# Right_Glove.net
KiCad netlist of a schematic drawn in EAGLE
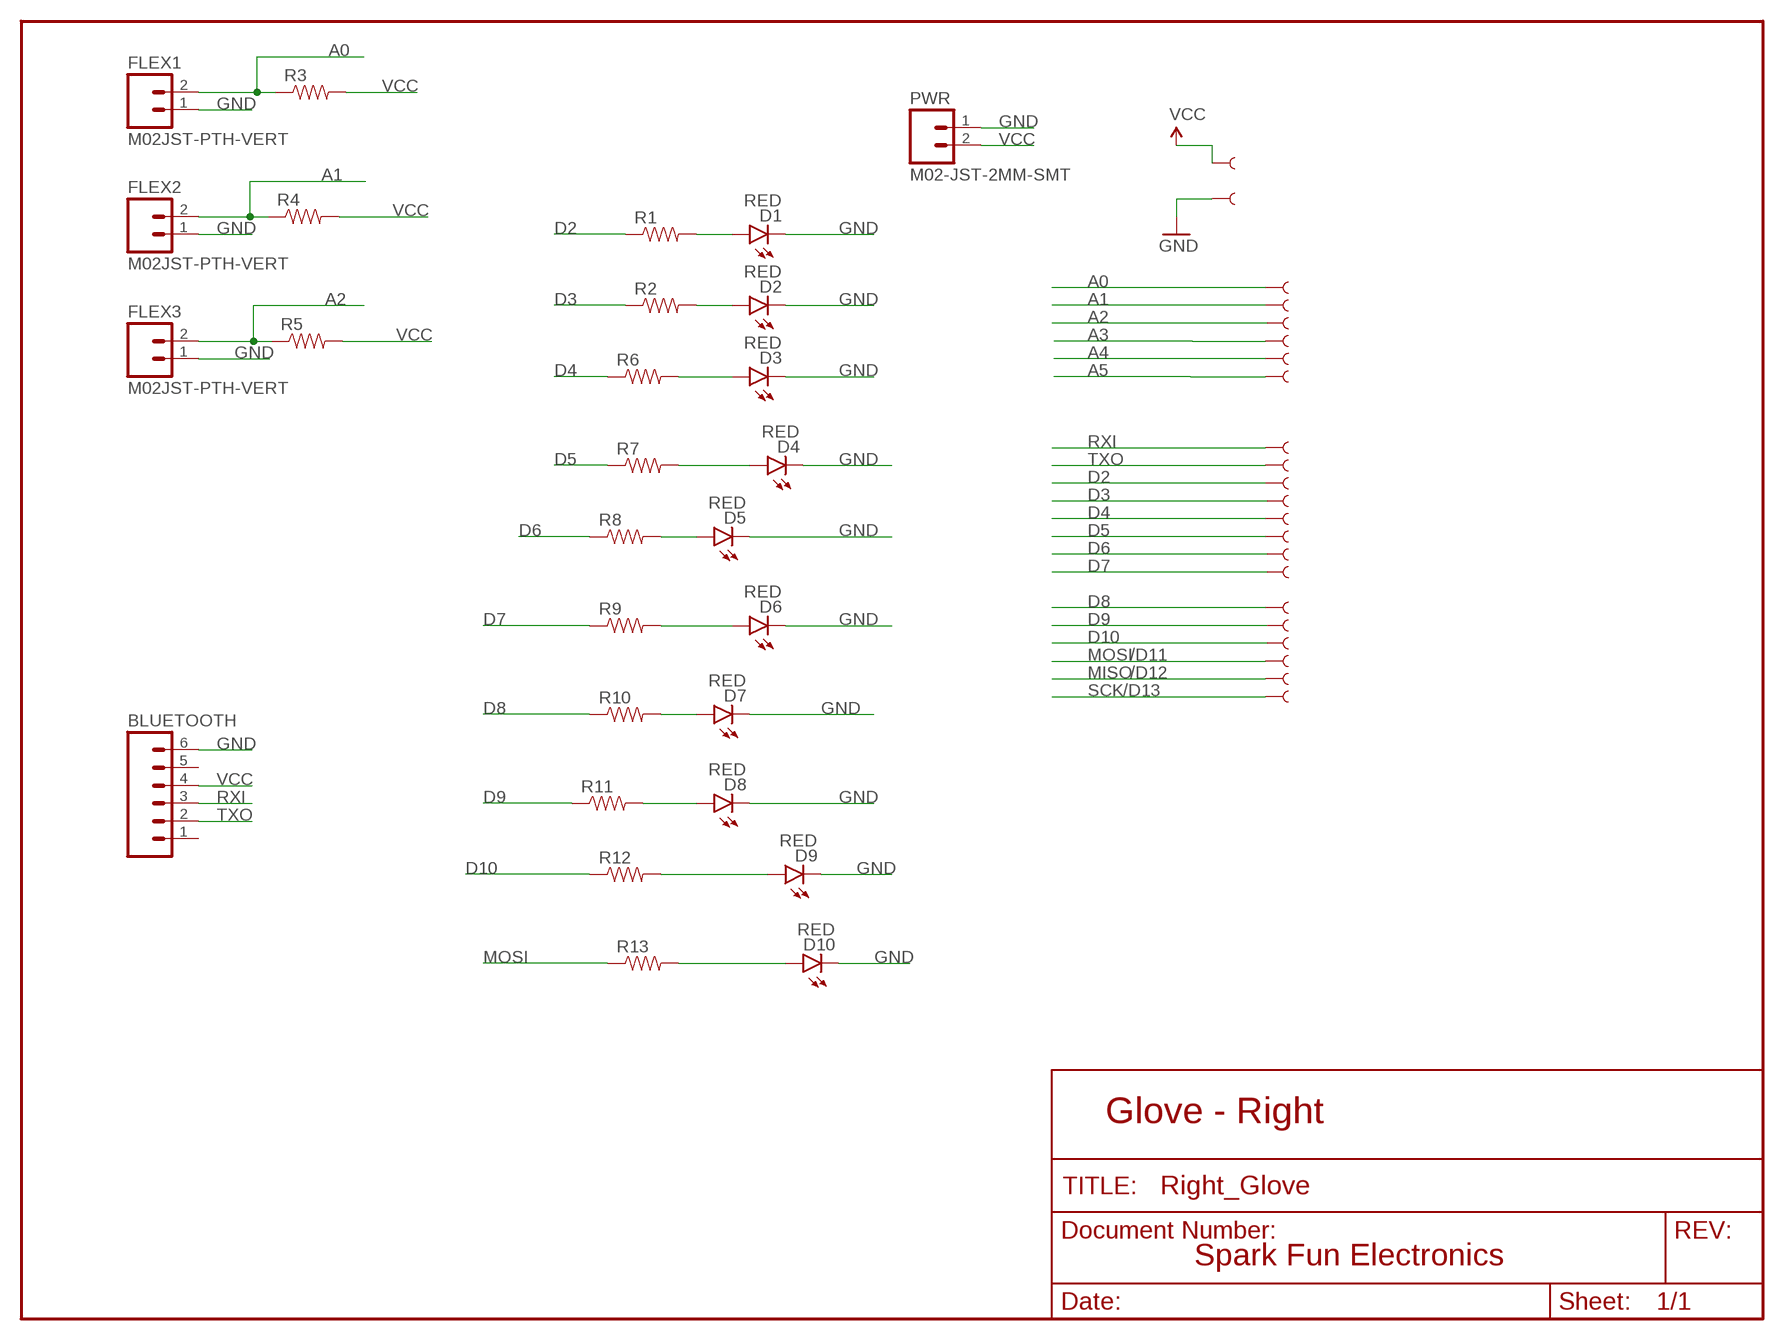
[diagram p0: schematic, sheet 1]

(export (version "E")
  (design (tool "Eeschema 10.0.6"))
  (components
    (comp (ref "BLUETOOTH")
      (value "M06LOCK")
      (footprint "eagle-import:1X06_LOCK")
      (libsource (lib "eagle-import") (part "M06LOCK"))
    )
    (comp (ref "D1")
      (value "RED")
      (footprint "eagle-import:LED-1206")
      (libsource (lib "eagle-import") (part "LED-RED1206"))
    )
    (comp (ref "D2")
      (value "RED")
      (footprint "eagle-import:LED-1206")
      (libsource (lib "eagle-import") (part "LED-RED1206"))
    )
    (comp (ref "D3")
      (value "RED")
      (footprint "eagle-import:LED-1206")
      (libsource (lib "eagle-import") (part "LED-RED1206"))
    )
    (comp (ref "D4")
      (value "RED")
      (footprint "eagle-import:LED-1206")
      (libsource (lib "eagle-import") (part "LED-RED1206"))
    )
    (comp (ref "D5")
      (value "RED")
      (footprint "eagle-import:LED-1206")
      (libsource (lib "eagle-import") (part "LED-RED1206"))
    )
    (comp (ref "D6")
      (value "RED")
      (footprint "eagle-import:LED-1206")
      (libsource (lib "eagle-import") (part "LED-RED1206"))
    )
    (comp (ref "D7")
      (value "RED")
      (footprint "eagle-import:LED-1206")
      (libsource (lib "eagle-import") (part "LED-RED1206"))
    )
    (comp (ref "D8")
      (value "RED")
      (footprint "eagle-import:LED-1206")
      (libsource (lib "eagle-import") (part "LED-RED1206"))
    )
    (comp (ref "D9")
      (value "RED")
      (footprint "eagle-import:LED-1206")
      (libsource (lib "eagle-import") (part "LED-RED1206"))
    )
    (comp (ref "D10")
      (value "RED")
      (footprint "eagle-import:LED-1206")
      (libsource (lib "eagle-import") (part "LED-RED1206"))
    )
    (comp (ref "FLEX1")
      (value "M02JST-PTH-VERT")
      (footprint "eagle-import:JST-2-PTH-VERT")
      (libsource (lib "eagle-import") (part "M02JST-PTH-VERT"))
    )
    (comp (ref "FLEX2")
      (value "M02JST-PTH-VERT")
      (footprint "eagle-import:JST-2-PTH-VERT")
      (libsource (lib "eagle-import") (part "M02JST-PTH-VERT"))
    )
    (comp (ref "FLEX3")
      (value "M02JST-PTH-VERT")
      (footprint "eagle-import:JST-2-PTH-VERT")
      (libsource (lib "eagle-import") (part "M02JST-PTH-VERT"))
    )
    (comp (ref "PWR")
      (value "M02-JST-2MM-SMT")
      (footprint "eagle-import:JST-2-SMD")
      (libsource (lib "eagle-import") (part "M02-JST-2MM-SMT"))
    )
    (comp (ref "R1")
      (value "RESISTOR1206")
      (footprint "eagle-import:1206")
      (libsource (lib "eagle-import") (part "RESISTOR1206"))
    )
    (comp (ref "R2")
      (value "RESISTOR1206")
      (footprint "eagle-import:1206")
      (libsource (lib "eagle-import") (part "RESISTOR1206"))
    )
    (comp (ref "R3")
      (value "RESISTOR1206")
      (footprint "eagle-import:1206")
      (libsource (lib "eagle-import") (part "RESISTOR1206"))
    )
    (comp (ref "R4")
      (value "RESISTOR1206")
      (footprint "eagle-import:1206")
      (libsource (lib "eagle-import") (part "RESISTOR1206"))
    )
    (comp (ref "R5")
      (value "RESISTOR1206")
      (footprint "eagle-import:1206")
      (libsource (lib "eagle-import") (part "RESISTOR1206"))
    )
    (comp (ref "R6")
      (value "RESISTOR1206")
      (footprint "eagle-import:1206")
      (libsource (lib "eagle-import") (part "RESISTOR1206"))
    )
    (comp (ref "R7")
      (value "RESISTOR1206")
      (footprint "eagle-import:1206")
      (libsource (lib "eagle-import") (part "RESISTOR1206"))
    )
    (comp (ref "R8")
      (value "RESISTOR1206")
      (footprint "eagle-import:1206")
      (libsource (lib "eagle-import") (part "RESISTOR1206"))
    )
    (comp (ref "R9")
      (value "RESISTOR1206")
      (footprint "eagle-import:1206")
      (libsource (lib "eagle-import") (part "RESISTOR1206"))
    )
    (comp (ref "R10")
      (value "RESISTOR1206")
      (footprint "eagle-import:1206")
      (libsource (lib "eagle-import") (part "RESISTOR1206"))
    )
    (comp (ref "R11")
      (value "RESISTOR1206")
      (footprint "eagle-import:1206")
      (libsource (lib "eagle-import") (part "RESISTOR1206"))
    )
    (comp (ref "R12")
      (value "RESISTOR1206")
      (footprint "eagle-import:1206")
      (libsource (lib "eagle-import") (part "RESISTOR1206"))
    )
    (comp (ref "R13")
      (value "RESISTOR1206")
      (footprint "eagle-import:1206")
      (libsource (lib "eagle-import") (part "RESISTOR1206"))
    )
    (comp (ref "U$22")
      (value "SEWTAP1")
      (footprint "eagle-import:PETAL-LONG-1")
      (libsource (lib "eagle-import") (part "SEWTAP1"))
    )
    (comp (ref "U$23")
      (value "SEWTAP1")
      (footprint "eagle-import:PETAL-LONG-1")
      (libsource (lib "eagle-import") (part "SEWTAP1"))
    )
    (comp (ref "U$24")
      (value "SEWTAP1")
      (footprint "eagle-import:PETAL-LONG-1")
      (libsource (lib "eagle-import") (part "SEWTAP1"))
    )
    (comp (ref "U$26")
      (value "SEWTAP1")
      (footprint "eagle-import:PETAL-LONG-1")
      (libsource (lib "eagle-import") (part "SEWTAP1"))
    )
    (comp (ref "U$27")
      (value "SEWTAP1")
      (footprint "eagle-import:PETAL-LONG-1")
      (libsource (lib "eagle-import") (part "SEWTAP1"))
    )
    (comp (ref "U$28")
      (value "SEWTAP1")
      (footprint "eagle-import:PETAL-LONG-1")
      (libsource (lib "eagle-import") (part "SEWTAP1"))
    )
    (comp (ref "U$29")
      (value "SEWTAP1")
      (footprint "eagle-import:PETAL-LONG-1")
      (libsource (lib "eagle-import") (part "SEWTAP1"))
    )
    (comp (ref "U$30")
      (value "SEWTAP1")
      (footprint "eagle-import:PETAL-LONG-1")
      (libsource (lib "eagle-import") (part "SEWTAP1"))
    )
    (comp (ref "U$31")
      (value "SEWTAP1")
      (footprint "eagle-import:PETAL-LONG-1")
      (libsource (lib "eagle-import") (part "SEWTAP1"))
    )
    (comp (ref "U$32")
      (value "SEWTAP1")
      (footprint "eagle-import:PETAL-LONG-1")
      (libsource (lib "eagle-import") (part "SEWTAP1"))
    )
    (comp (ref "U$33")
      (value "SEWTAP1")
      (footprint "eagle-import:PETAL-LONG-1")
      (libsource (lib "eagle-import") (part "SEWTAP1"))
    )
    (comp (ref "U$34")
      (value "SEWTAP1")
      (footprint "eagle-import:PETAL-LONG-1")
      (libsource (lib "eagle-import") (part "SEWTAP1"))
    )
    (comp (ref "U$35")
      (value "SEWTAP1")
      (footprint "eagle-import:PETAL-LONG-1")
      (libsource (lib "eagle-import") (part "SEWTAP1"))
    )
    (comp (ref "U$36")
      (value "SEWTAP1")
      (footprint "eagle-import:PETAL-LONG-1")
      (libsource (lib "eagle-import") (part "SEWTAP1"))
    )
    (comp (ref "U$37")
      (value "SEWTAP1")
      (footprint "eagle-import:PETAL-LONG-1")
      (libsource (lib "eagle-import") (part "SEWTAP1"))
    )
    (comp (ref "U$38")
      (value "SEWTAP1")
      (footprint "eagle-import:PETAL-LONG-1")
      (libsource (lib "eagle-import") (part "SEWTAP1"))
    )
    (comp (ref "U$39")
      (value "SEWTAP1")
      (footprint "eagle-import:PETAL-LONG-1")
      (libsource (lib "eagle-import") (part "SEWTAP1"))
    )
    (comp (ref "U$40")
      (value "SEWTAP1")
      (footprint "eagle-import:PETAL-LONG-1")
      (libsource (lib "eagle-import") (part "SEWTAP1"))
    )
    (comp (ref "U$41")
      (value "SEWTAP1")
      (footprint "eagle-import:PETAL-LONG-1")
      (libsource (lib "eagle-import") (part "SEWTAP1"))
    )
    (comp (ref "U$42")
      (value "SEWTAP1")
      (footprint "eagle-import:PETAL-LONG-1")
      (libsource (lib "eagle-import") (part "SEWTAP1"))
    )
    (comp (ref "U$43")
      (value "SEWTAP1")
      (footprint "eagle-import:PETAL-LONG-1")
      (libsource (lib "eagle-import") (part "SEWTAP1"))
    )
    (comp (ref "U$44")
      (value "SEWTAP1")
      (footprint "eagle-import:PETAL-LONG-1")
      (libsource (lib "eagle-import") (part "SEWTAP1"))
    )
  )
  (nets
    (net (code "1") (name "/A0") (class "Default")
      (node (ref "FLEX1") (pin "2") (pinfunction "2_2") (pintype "passive"))
      (node (ref "R3") (pin "1") (pinfunction "1_1") (pintype "passive"))
      (node (ref "U$24") (pin "P$1") (pinfunction "1_P$1") (pintype "bidirectional"))
    )
    (net (code "2") (name "/A1") (class "Default")
      (node (ref "FLEX2") (pin "2") (pinfunction "2_2") (pintype "passive"))
      (node (ref "R4") (pin "1") (pinfunction "1_1") (pintype "passive"))
      (node (ref "U$26") (pin "P$1") (pinfunction "1_P$1") (pintype "bidirectional"))
    )
    (net (code "3") (name "/A2") (class "Default")
      (node (ref "FLEX3") (pin "2") (pinfunction "2_2") (pintype "passive"))
      (node (ref "R5") (pin "1") (pinfunction "1_1") (pintype "passive"))
      (node (ref "U$27") (pin "P$1") (pinfunction "1_P$1") (pintype "bidirectional"))
    )
    (net (code "4") (name "/A3") (class "Default")
      (node (ref "U$28") (pin "P$1") (pinfunction "1_P$1") (pintype "bidirectional"))
    )
    (net (code "5") (name "/A4") (class "Default")
      (node (ref "U$29") (pin "P$1") (pinfunction "1_P$1") (pintype "bidirectional"))
    )
    (net (code "6") (name "/A5") (class "Default")
      (node (ref "U$30") (pin "P$1") (pinfunction "1_P$1") (pintype "bidirectional"))
    )
    (net (code "7") (name "/D2") (class "Default")
      (node (ref "R1") (pin "1") (pinfunction "1_1") (pintype "passive"))
      (node (ref "U$33") (pin "P$1") (pinfunction "1_P$1") (pintype "bidirectional"))
    )
    (net (code "8") (name "/D3") (class "Default")
      (node (ref "R2") (pin "1") (pinfunction "1_1") (pintype "passive"))
      (node (ref "U$34") (pin "P$1") (pinfunction "1_P$1") (pintype "bidirectional"))
    )
    (net (code "9") (name "/D4") (class "Default")
      (node (ref "R6") (pin "1") (pinfunction "1_1") (pintype "passive"))
      (node (ref "U$35") (pin "P$1") (pinfunction "1_P$1") (pintype "bidirectional"))
    )
    (net (code "10") (name "/D5") (class "Default")
      (node (ref "R7") (pin "1") (pinfunction "1_1") (pintype "passive"))
      (node (ref "U$36") (pin "P$1") (pinfunction "1_P$1") (pintype "bidirectional"))
    )
    (net (code "11") (name "/D6") (class "Default")
      (node (ref "R8") (pin "1") (pinfunction "1_1") (pintype "passive"))
      (node (ref "U$37") (pin "P$1") (pinfunction "1_P$1") (pintype "bidirectional"))
    )
    (net (code "12") (name "/D7") (class "Default")
      (node (ref "R9") (pin "1") (pinfunction "1_1") (pintype "passive"))
      (node (ref "U$38") (pin "P$1") (pinfunction "1_P$1") (pintype "bidirectional"))
    )
    (net (code "13") (name "/D8") (class "Default")
      (node (ref "R10") (pin "1") (pinfunction "1_1") (pintype "passive"))
      (node (ref "U$39") (pin "P$1") (pinfunction "1_P$1") (pintype "bidirectional"))
    )
    (net (code "14") (name "/D9") (class "Default")
      (node (ref "R11") (pin "1") (pinfunction "1_1") (pintype "passive"))
      (node (ref "U$40") (pin "P$1") (pinfunction "1_P$1") (pintype "bidirectional"))
    )
    (net (code "15") (name "/D10") (class "Default")
      (node (ref "R12") (pin "1") (pinfunction "1_1") (pintype "passive"))
      (node (ref "U$41") (pin "P$1") (pinfunction "1_P$1") (pintype "bidirectional"))
    )
    (net (code "16") (name "/MISO") (class "Default")
      (node (ref "U$43") (pin "P$1") (pinfunction "1_P$1") (pintype "bidirectional"))
    )
    (net (code "17") (name "/MOSI") (class "Default")
      (node (ref "R13") (pin "1") (pinfunction "1_1") (pintype "passive"))
      (node (ref "U$42") (pin "P$1") (pinfunction "1_P$1") (pintype "bidirectional"))
    )
    (net (code "18") (name "/RXI") (class "Default")
      (node (ref "BLUETOOTH") (pin "3") (pinfunction "3_3") (pintype "passive"))
      (node (ref "U$31") (pin "P$1") (pinfunction "1_P$1") (pintype "bidirectional"))
    )
    (net (code "19") (name "/SCK") (class "Default")
      (node (ref "U$44") (pin "P$1") (pinfunction "1_P$1") (pintype "bidirectional"))
    )
    (net (code "20") (name "/TXO") (class "Default")
      (node (ref "BLUETOOTH") (pin "2") (pinfunction "2_2") (pintype "passive"))
      (node (ref "U$32") (pin "P$1") (pinfunction "1_P$1") (pintype "bidirectional"))
    )
    (net (code "21") (name "GND") (class "Default")
      (node (ref "BLUETOOTH") (pin "6") (pinfunction "6_6") (pintype "passive"))
      (node (ref "D1") (pin "C") (pinfunction "C_C") (pintype "passive"))
      (node (ref "D10") (pin "C") (pinfunction "C_C") (pintype "passive"))
      (node (ref "D2") (pin "C") (pinfunction "C_C") (pintype "passive"))
      (node (ref "D3") (pin "C") (pinfunction "C_C") (pintype "passive"))
      (node (ref "D4") (pin "C") (pinfunction "C_C") (pintype "passive"))
      (node (ref "D5") (pin "C") (pinfunction "C_C") (pintype "passive"))
      (node (ref "D6") (pin "C") (pinfunction "C_C") (pintype "passive"))
      (node (ref "D7") (pin "C") (pinfunction "C_C") (pintype "passive"))
      (node (ref "D8") (pin "C") (pinfunction "C_C") (pintype "passive"))
      (node (ref "D9") (pin "C") (pinfunction "C_C") (pintype "passive"))
      (node (ref "FLEX1") (pin "1") (pinfunction "1_1") (pintype "passive"))
      (node (ref "FLEX2") (pin "1") (pinfunction "1_1") (pintype "passive"))
      (node (ref "FLEX3") (pin "1") (pinfunction "1_1") (pintype "passive"))
      (node (ref "PWR") (pin "1") (pinfunction "2_1") (pintype "passive"))
      (node (ref "U$23") (pin "P$1") (pinfunction "1_P$1") (pintype "bidirectional"))
    )
    (net (code "22") (name "Net-(D1-PadA)") (class "Default")
      (node (ref "D1") (pin "A") (pinfunction "A_A") (pintype "passive"))
      (node (ref "R1") (pin "2") (pinfunction "2_2") (pintype "passive"))
    )
    (net (code "23") (name "Net-(D2-PadA)") (class "Default")
      (node (ref "D2") (pin "A") (pinfunction "A_A") (pintype "passive"))
      (node (ref "R2") (pin "2") (pinfunction "2_2") (pintype "passive"))
    )
    (net (code "24") (name "Net-(D3-PadA)") (class "Default")
      (node (ref "D3") (pin "A") (pinfunction "A_A") (pintype "passive"))
      (node (ref "R6") (pin "2") (pinfunction "2_2") (pintype "passive"))
    )
    (net (code "25") (name "Net-(D4-PadA)") (class "Default")
      (node (ref "D4") (pin "A") (pinfunction "A_A") (pintype "passive"))
      (node (ref "R7") (pin "2") (pinfunction "2_2") (pintype "passive"))
    )
    (net (code "26") (name "Net-(D5-PadA)") (class "Default")
      (node (ref "D5") (pin "A") (pinfunction "A_A") (pintype "passive"))
      (node (ref "R8") (pin "2") (pinfunction "2_2") (pintype "passive"))
    )
    (net (code "27") (name "Net-(D6-PadA)") (class "Default")
      (node (ref "D6") (pin "A") (pinfunction "A_A") (pintype "passive"))
      (node (ref "R9") (pin "2") (pinfunction "2_2") (pintype "passive"))
    )
    (net (code "28") (name "Net-(D7-PadA)") (class "Default")
      (node (ref "D7") (pin "A") (pinfunction "A_A") (pintype "passive"))
      (node (ref "R10") (pin "2") (pinfunction "2_2") (pintype "passive"))
    )
    (net (code "29") (name "Net-(D8-PadA)") (class "Default")
      (node (ref "D8") (pin "A") (pinfunction "A_A") (pintype "passive"))
      (node (ref "R11") (pin "2") (pinfunction "2_2") (pintype "passive"))
    )
    (net (code "30") (name "Net-(D9-PadA)") (class "Default")
      (node (ref "D9") (pin "A") (pinfunction "A_A") (pintype "passive"))
      (node (ref "R12") (pin "2") (pinfunction "2_2") (pintype "passive"))
    )
    (net (code "31") (name "Net-(D10-PadA)") (class "Default")
      (node (ref "D10") (pin "A") (pinfunction "A_A") (pintype "passive"))
      (node (ref "R13") (pin "2") (pinfunction "2_2") (pintype "passive"))
    )
    (net (code "32") (name "VCC") (class "Default")
      (node (ref "BLUETOOTH") (pin "4") (pinfunction "4_4") (pintype "passive"))
      (node (ref "PWR") (pin "2") (pinfunction "1_2") (pintype "passive"))
      (node (ref "R3") (pin "2") (pinfunction "2_2") (pintype "passive"))
      (node (ref "R4") (pin "2") (pinfunction "2_2") (pintype "passive"))
      (node (ref "R5") (pin "2") (pinfunction "2_2") (pintype "passive"))
      (node (ref "U$22") (pin "P$1") (pinfunction "1_P$1") (pintype "bidirectional"))
    )
    (net (code "33") (name "unconnected-(BLUETOOTH-Pad1)") (class "Default")
      (node (ref "BLUETOOTH") (pin "1") (pinfunction "1_1") (pintype "passive"))
    )
    (net (code "34") (name "unconnected-(BLUETOOTH-Pad5)") (class "Default")
      (node (ref "BLUETOOTH") (pin "5") (pinfunction "5_5") (pintype "passive"))
    )
  )
)
